# IDC_BNC_Adapter.net
KiCad netlist of a schematic drawn in Altium Designer
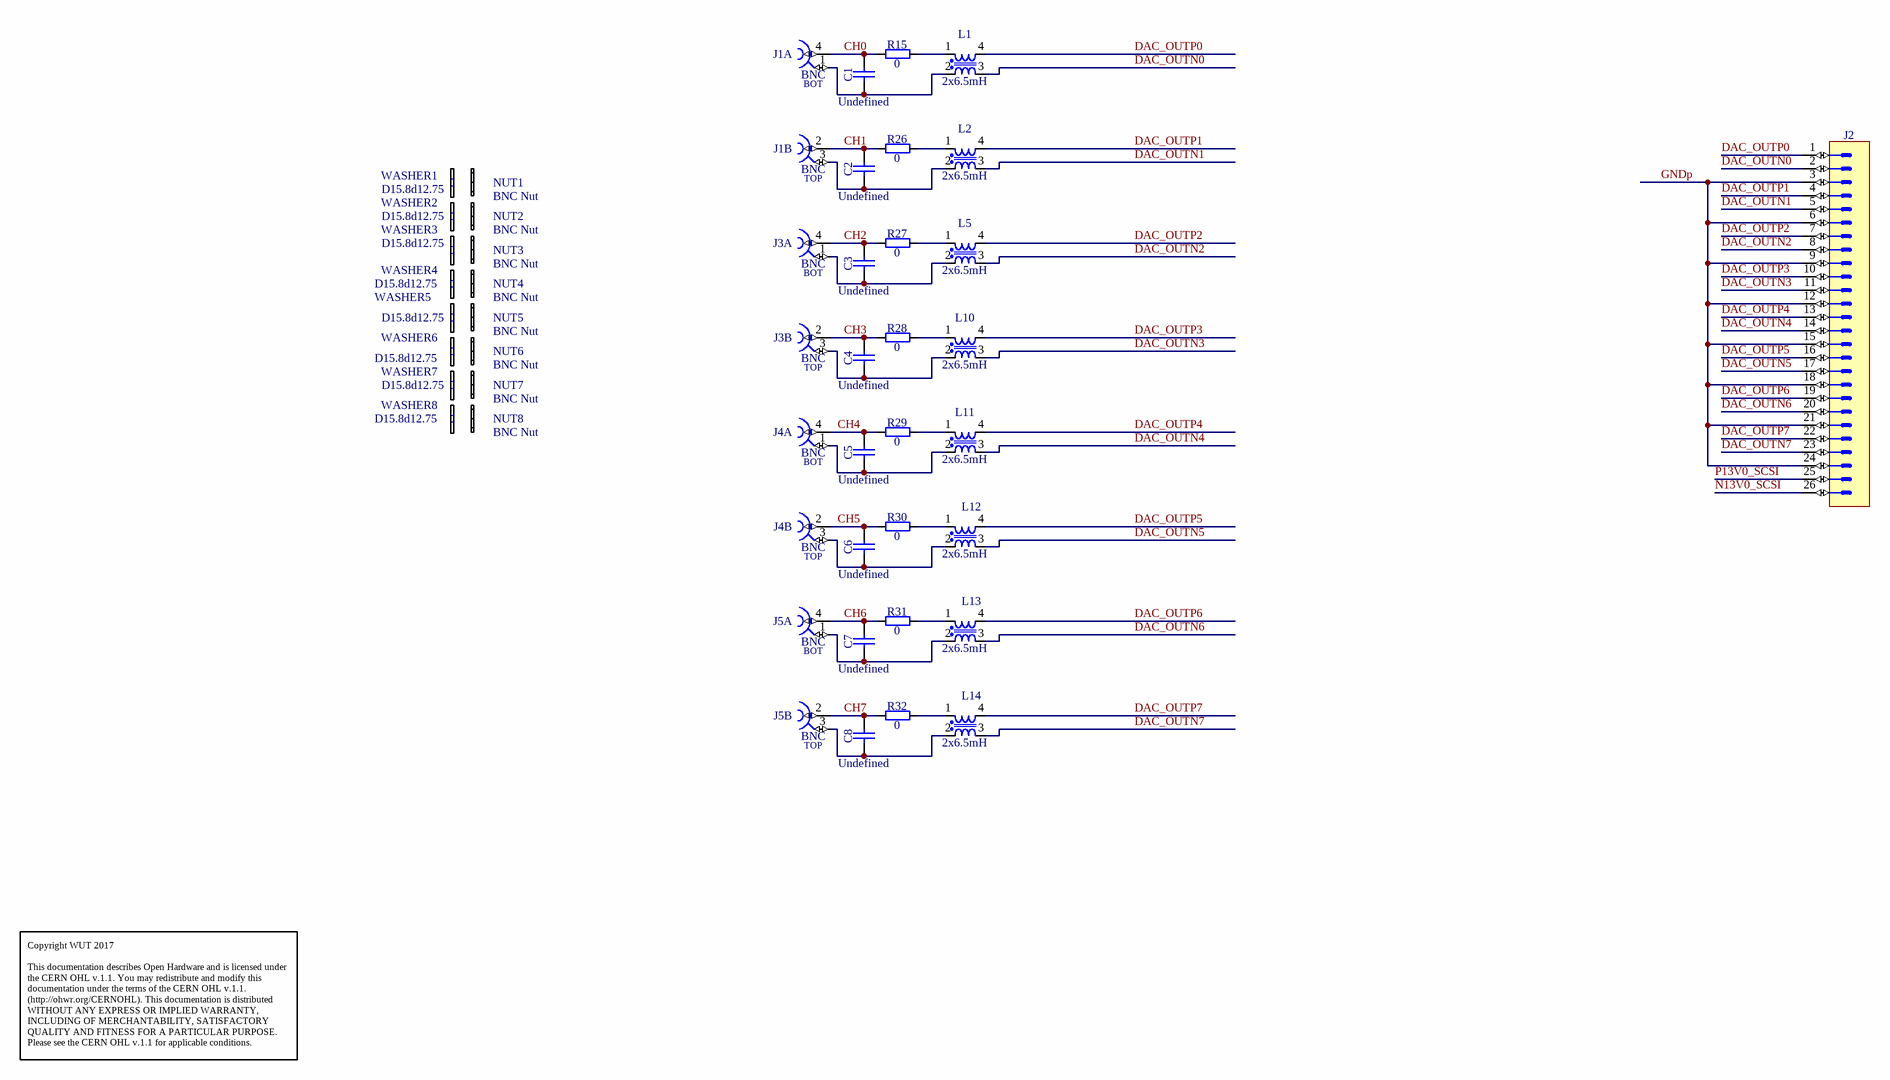
[diagram p0: IDC_BNC_Adapter.SchDoc]

(export (version "E")
  (design (tool "Eeschema 10.0.6"))
  (components
    (comp (ref "C1")
      (value "Undefined")
      (footprint "CAPC2012X135N")
      (description "Non-polarised capacitor")
      (fields (field (name "PART NUMBER") "CC0805_NO-VALUE") (field (name "AUTHOR") "CERN DEM JLC"))
      (libsource (lib "Capacitors") (part "Capacitor - non polarized"))
    )
    (comp (ref "C2")
      (value "Undefined")
      (footprint "CAPC2012X135N")
      (description "Non-polarised capacitor")
      (fields (field (name "PART NUMBER") "CC0805_NO-VALUE") (field (name "AUTHOR") "CERN DEM JLC"))
      (libsource (lib "Capacitors") (part "Capacitor - non polarized"))
    )
    (comp (ref "C3")
      (value "Undefined")
      (footprint "CAPC2012X135N")
      (description "Non-polarised capacitor")
      (fields (field (name "PART NUMBER") "CC0805_NO-VALUE") (field (name "AUTHOR") "CERN DEM JLC"))
      (libsource (lib "Capacitors") (part "Capacitor - non polarized"))
    )
    (comp (ref "C4")
      (value "Undefined")
      (footprint "CAPC2012X135N")
      (description "Non-polarised capacitor")
      (fields (field (name "PART NUMBER") "CC0805_NO-VALUE") (field (name "AUTHOR") "CERN DEM JLC"))
      (libsource (lib "Capacitors") (part "Capacitor - non polarized"))
    )
    (comp (ref "C5")
      (value "Undefined")
      (footprint "CAPC2012X135N")
      (description "Non-polarised capacitor")
      (fields (field (name "PART NUMBER") "CC0805_NO-VALUE") (field (name "AUTHOR") "CERN DEM JLC"))
      (libsource (lib "Capacitors") (part "Capacitor - non polarized"))
    )
    (comp (ref "C6")
      (value "Undefined")
      (footprint "CAPC2012X135N")
      (description "Non-polarised capacitor")
      (fields (field (name "PART NUMBER") "CC0805_NO-VALUE") (field (name "AUTHOR") "CERN DEM JLC"))
      (libsource (lib "Capacitors") (part "Capacitor - non polarized"))
    )
    (comp (ref "C7")
      (value "Undefined")
      (footprint "CAPC2012X135N")
      (description "Non-polarised capacitor")
      (fields (field (name "PART NUMBER") "CC0805_NO-VALUE") (field (name "AUTHOR") "CERN DEM JLC"))
      (libsource (lib "Capacitors") (part "Capacitor - non polarized"))
    )
    (comp (ref "C8")
      (value "Undefined")
      (footprint "CAPC2012X135N")
      (description "Non-polarised capacitor")
      (fields (field (name "PART NUMBER") "CC0805_NO-VALUE") (field (name "AUTHOR") "CERN DEM JLC"))
      (libsource (lib "Capacitors") (part "Capacitor - non polarized"))
    )
    (comp (ref "J1")
      (value "BNC")
      (footprint "RENHOTEC_RHT-610-0049")
      (description "Dual Right Angle 50 Ohm BNC Jack, White Valox Case")
      (fields
        (field (name "PART NUMBER") "RENHOTEC_RHT-610-0049")
        (field (name "MANUFACTURER") "RENHOTEC")
        (field (name "AUTHOR") "GK")
      )
      (libsource (lib "LIBRARY_SCH") (part "CON_BNC_DUAL"))
    )
    (comp (ref "J2")
      (value "Header 26")
      (footprint "3M_N2526-6003RB")
      (description "Connector 26 Male")
      (fields
        (field (name "PART NUMBER") "3M_N2526-6003RB")
        (field (name "MANUFACTURER") "3M")
        (field (name "AUTHOR") "CERN DEM JLC")
      )
      (libsource (lib "Connectors") (part "Connector 26 Male"))
    )
    (comp (ref "J3")
      (value "BNC")
      (footprint "RENHOTEC_RHT-610-0049")
      (description "Dual Right Angle 50 Ohm BNC Jack, White Valox Case")
      (fields
        (field (name "PART NUMBER") "RENHOTEC_RHT-610-0049")
        (field (name "MANUFACTURER") "RENHOTEC")
        (field (name "AUTHOR") "GK")
      )
      (libsource (lib "LIBRARY_SCH") (part "CON_BNC_DUAL"))
    )
    (comp (ref "J4")
      (value "BNC")
      (footprint "RENHOTEC_RHT-610-0049")
      (description "Dual Right Angle 50 Ohm BNC Jack, White Valox Case")
      (fields
        (field (name "PART NUMBER") "RENHOTEC_RHT-610-0049")
        (field (name "MANUFACTURER") "RENHOTEC")
        (field (name "AUTHOR") "GK")
      )
      (libsource (lib "LIBRARY_SCH") (part "CON_BNC_DUAL"))
    )
    (comp (ref "J5")
      (value "BNC")
      (footprint "RENHOTEC_RHT-610-0049")
      (description "Dual Right Angle 50 Ohm BNC Jack, White Valox Case")
      (fields
        (field (name "PART NUMBER") "RENHOTEC_RHT-610-0049")
        (field (name "MANUFACTURER") "RENHOTEC")
        (field (name "AUTHOR") "GK")
      )
      (libsource (lib "LIBRARY_SCH") (part "CON_BNC_DUAL"))
    )
    (comp (ref "L1")
      (value "2x6.5mH")
      (footprint "IND_WURTH_WE-SL2")
      (description "Inductor Common Mode")
      (fields
        (field (name "PART NUMBER") "IND_6.5MH_50%_WURTH_WE-SL2-744229")
        (field (name "POWER") "400mA")
        (field (name "AUTHOR") "CERN DEM JLC")
      )
      (libsource (lib "Inductors & Transformers") (part "Inductor Common Mode 1Dot-4 2Dot-3"))
    )
    (comp (ref "L2")
      (value "2x6.5mH")
      (footprint "IND_WURTH_WE-SL2")
      (description "Inductor Common Mode")
      (fields
        (field (name "PART NUMBER") "IND_6.5MH_50%_WURTH_WE-SL2-744229")
        (field (name "POWER") "400mA")
        (field (name "AUTHOR") "CERN DEM JLC")
      )
      (libsource (lib "Inductors & Transformers") (part "Inductor Common Mode 1Dot-4 2Dot-3"))
    )
    (comp (ref "L5")
      (value "2x6.5mH")
      (footprint "IND_WURTH_WE-SL2")
      (description "Inductor Common Mode")
      (fields
        (field (name "PART NUMBER") "IND_6.5MH_50%_WURTH_WE-SL2-744229")
        (field (name "POWER") "400mA")
        (field (name "AUTHOR") "CERN DEM JLC")
      )
      (libsource (lib "Inductors & Transformers") (part "Inductor Common Mode 1Dot-4 2Dot-3"))
    )
    (comp (ref "L10")
      (value "2x6.5mH")
      (footprint "IND_WURTH_WE-SL2")
      (description "Inductor Common Mode")
      (fields
        (field (name "PART NUMBER") "IND_6.5MH_50%_WURTH_WE-SL2-744229")
        (field (name "POWER") "400mA")
        (field (name "AUTHOR") "CERN DEM JLC")
      )
      (libsource (lib "Inductors & Transformers") (part "Inductor Common Mode 1Dot-4 2Dot-3"))
    )
    (comp (ref "L11")
      (value "2x6.5mH")
      (footprint "IND_WURTH_WE-SL2")
      (description "Inductor Common Mode")
      (fields
        (field (name "PART NUMBER") "IND_6.5MH_50%_WURTH_WE-SL2-744229")
        (field (name "POWER") "400mA")
        (field (name "AUTHOR") "CERN DEM JLC")
      )
      (libsource (lib "Inductors & Transformers") (part "Inductor Common Mode 1Dot-4 2Dot-3"))
    )
    (comp (ref "L12")
      (value "2x6.5mH")
      (footprint "IND_WURTH_WE-SL2")
      (description "Inductor Common Mode")
      (fields
        (field (name "PART NUMBER") "IND_6.5MH_50%_WURTH_WE-SL2-744229")
        (field (name "POWER") "400mA")
        (field (name "AUTHOR") "CERN DEM JLC")
      )
      (libsource (lib "Inductors & Transformers") (part "Inductor Common Mode 1Dot-4 2Dot-3"))
    )
    (comp (ref "L13")
      (value "2x6.5mH")
      (footprint "IND_WURTH_WE-SL2")
      (description "Inductor Common Mode")
      (fields
        (field (name "PART NUMBER") "IND_6.5MH_50%_WURTH_WE-SL2-744229")
        (field (name "POWER") "400mA")
        (field (name "AUTHOR") "CERN DEM JLC")
      )
      (libsource (lib "Inductors & Transformers") (part "Inductor Common Mode 1Dot-4 2Dot-3"))
    )
    (comp (ref "L14")
      (value "2x6.5mH")
      (footprint "IND_WURTH_WE-SL2")
      (description "Inductor Common Mode")
      (fields
        (field (name "PART NUMBER") "IND_6.5MH_50%_WURTH_WE-SL2-744229")
        (field (name "POWER") "400mA")
        (field (name "AUTHOR") "CERN DEM JLC")
      )
      (libsource (lib "Inductors & Transformers") (part "Inductor Common Mode 1Dot-4 2Dot-3"))
    )
    (comp (ref "NUT1")
      (value "BNC Nut")
      (footprint "TE_1-329631-2")
      (description "BNC nut")
      (fields
        (field (name "PART NUMBER") "TE_1-329631-2")
        (field (name "MANUFACTURER") "TE")
        (field (name "AUTHOR") "CERN DEM JLC")
      )
      (libsource (lib "LIBRARY_SCH") (part "MECH_BNC_NUT"))
    )
    (comp (ref "NUT2")
      (value "BNC Nut")
      (footprint "TE_1-329631-2")
      (description "BNC nut")
      (fields
        (field (name "PART NUMBER") "TE_1-329631-2")
        (field (name "MANUFACTURER") "TE")
        (field (name "AUTHOR") "CERN DEM JLC")
      )
      (libsource (lib "LIBRARY_SCH") (part "MECH_BNC_NUT"))
    )
    (comp (ref "NUT3")
      (value "BNC Nut")
      (footprint "TE_1-329631-2")
      (description "BNC nut")
      (fields
        (field (name "PART NUMBER") "TE_1-329631-2")
        (field (name "MANUFACTURER") "TE")
        (field (name "AUTHOR") "CERN DEM JLC")
      )
      (libsource (lib "LIBRARY_SCH") (part "MECH_BNC_NUT"))
    )
    (comp (ref "NUT4")
      (value "BNC Nut")
      (footprint "TE_1-329631-2")
      (description "BNC nut")
      (fields
        (field (name "PART NUMBER") "TE_1-329631-2")
        (field (name "MANUFACTURER") "TE")
        (field (name "AUTHOR") "CERN DEM JLC")
      )
      (libsource (lib "LIBRARY_SCH") (part "MECH_BNC_NUT"))
    )
    (comp (ref "NUT5")
      (value "BNC Nut")
      (footprint "TE_1-329631-2")
      (description "BNC nut")
      (fields
        (field (name "PART NUMBER") "TE_1-329631-2")
        (field (name "MANUFACTURER") "TE")
        (field (name "AUTHOR") "CERN DEM JLC")
      )
      (libsource (lib "LIBRARY_SCH") (part "MECH_BNC_NUT"))
    )
    (comp (ref "NUT6")
      (value "BNC Nut")
      (footprint "TE_1-329631-2")
      (description "BNC nut")
      (fields
        (field (name "PART NUMBER") "TE_1-329631-2")
        (field (name "MANUFACTURER") "TE")
        (field (name "AUTHOR") "CERN DEM JLC")
      )
      (libsource (lib "LIBRARY_SCH") (part "MECH_BNC_NUT"))
    )
    (comp (ref "NUT7")
      (value "BNC Nut")
      (footprint "TE_1-329631-2")
      (description "BNC nut")
      (fields
        (field (name "PART NUMBER") "TE_1-329631-2")
        (field (name "MANUFACTURER") "TE")
        (field (name "AUTHOR") "CERN DEM JLC")
      )
      (libsource (lib "LIBRARY_SCH") (part "MECH_BNC_NUT"))
    )
    (comp (ref "NUT8")
      (value "BNC Nut")
      (footprint "TE_1-329631-2")
      (description "BNC nut")
      (fields
        (field (name "PART NUMBER") "TE_1-329631-2")
        (field (name "MANUFACTURER") "TE")
        (field (name "AUTHOR") "CERN DEM JLC")
      )
      (libsource (lib "LIBRARY_SCH") (part "MECH_BNC_NUT"))
    )
    (comp (ref "R15")
      (value "0")
      (footprint "RESC1608X55N")
      (description "Resistor")
      (fields
        (field (name "PART NUMBER") "R0603_0R_JUMPER")
        (field (name "MANUFACTURER") "GENERIC")
        (field (name "AUTHOR") "CERN DEM JLC")
      )
      (libsource (lib "Resistors") (part "Resistor"))
    )
    (comp (ref "R26")
      (value "0")
      (footprint "RESC1608X55N")
      (description "Resistor")
      (fields
        (field (name "PART NUMBER") "R0603_0R_JUMPER")
        (field (name "MANUFACTURER") "GENERIC")
        (field (name "AUTHOR") "CERN DEM JLC")
      )
      (libsource (lib "Resistors") (part "Resistor"))
    )
    (comp (ref "R27")
      (value "0")
      (footprint "RESC1608X55N")
      (description "Resistor")
      (fields
        (field (name "PART NUMBER") "R0603_0R_JUMPER")
        (field (name "MANUFACTURER") "GENERIC")
        (field (name "AUTHOR") "CERN DEM JLC")
      )
      (libsource (lib "Resistors") (part "Resistor"))
    )
    (comp (ref "R28")
      (value "0")
      (footprint "RESC1608X55N")
      (description "Resistor")
      (fields
        (field (name "PART NUMBER") "R0603_0R_JUMPER")
        (field (name "MANUFACTURER") "GENERIC")
        (field (name "AUTHOR") "CERN DEM JLC")
      )
      (libsource (lib "Resistors") (part "Resistor"))
    )
    (comp (ref "R29")
      (value "0")
      (footprint "RESC1608X55N")
      (description "Resistor")
      (fields
        (field (name "PART NUMBER") "R0603_0R_JUMPER")
        (field (name "MANUFACTURER") "GENERIC")
        (field (name "AUTHOR") "CERN DEM JLC")
      )
      (libsource (lib "Resistors") (part "Resistor"))
    )
    (comp (ref "R30")
      (value "0")
      (footprint "RESC1608X55N")
      (description "Resistor")
      (fields
        (field (name "PART NUMBER") "R0603_0R_JUMPER")
        (field (name "MANUFACTURER") "GENERIC")
        (field (name "AUTHOR") "CERN DEM JLC")
      )
      (libsource (lib "Resistors") (part "Resistor"))
    )
    (comp (ref "R31")
      (value "0")
      (footprint "RESC1608X55N")
      (description "Resistor")
      (fields
        (field (name "PART NUMBER") "R0603_0R_JUMPER")
        (field (name "MANUFACTURER") "GENERIC")
        (field (name "AUTHOR") "CERN DEM JLC")
      )
      (libsource (lib "Resistors") (part "Resistor"))
    )
    (comp (ref "R32")
      (value "0")
      (footprint "RESC1608X55N")
      (description "Resistor")
      (fields
        (field (name "PART NUMBER") "R0603_0R_JUMPER")
        (field (name "MANUFACTURER") "GENERIC")
        (field (name "AUTHOR") "CERN DEM JLC")
      )
      (libsource (lib "Resistors") (part "Resistor"))
    )
    (comp (ref "WASHER1")
      (value "D15.8d12.75")
      (footprint "TE_1-1634817-0")
      (description "BNC Washer")
      (fields
        (field (name "PART NUMBER") "TE_1-1634817-0")
        (field (name "MANUFACTURER") "TE")
        (field (name "AUTHOR") "GK")
      )
      (libsource (lib "LIBRARY_SCH") (part "MECH_BNC_WASHER"))
    )
    (comp (ref "WASHER2")
      (value "D15.8d12.75")
      (footprint "TE_1-1634817-0")
      (description "BNC Washer")
      (fields
        (field (name "PART NUMBER") "TE_1-1634817-0")
        (field (name "MANUFACTURER") "TE")
        (field (name "AUTHOR") "GK")
      )
      (libsource (lib "LIBRARY_SCH") (part "MECH_BNC_WASHER"))
    )
    (comp (ref "WASHER3")
      (value "D15.8d12.75")
      (footprint "TE_1-1634817-0")
      (description "BNC Washer")
      (fields
        (field (name "PART NUMBER") "TE_1-1634817-0")
        (field (name "MANUFACTURER") "TE")
        (field (name "AUTHOR") "GK")
      )
      (libsource (lib "LIBRARY_SCH") (part "MECH_BNC_WASHER"))
    )
    (comp (ref "WASHER4")
      (value "D15.8d12.75")
      (footprint "TE_1-1634817-0")
      (description "BNC Washer")
      (fields
        (field (name "PART NUMBER") "TE_1-1634817-0")
        (field (name "MANUFACTURER") "TE")
        (field (name "AUTHOR") "GK")
      )
      (libsource (lib "LIBRARY_SCH") (part "MECH_BNC_WASHER"))
    )
    (comp (ref "WASHER5")
      (value "D15.8d12.75")
      (footprint "TE_1-1634817-0")
      (description "BNC Washer")
      (fields
        (field (name "PART NUMBER") "TE_1-1634817-0")
        (field (name "MANUFACTURER") "TE")
        (field (name "AUTHOR") "GK")
      )
      (libsource (lib "LIBRARY_SCH") (part "MECH_BNC_WASHER"))
    )
    (comp (ref "WASHER6")
      (value "D15.8d12.75")
      (footprint "TE_1-1634817-0")
      (description "BNC Washer")
      (fields
        (field (name "PART NUMBER") "TE_1-1634817-0")
        (field (name "MANUFACTURER") "TE")
        (field (name "AUTHOR") "GK")
      )
      (libsource (lib "LIBRARY_SCH") (part "MECH_BNC_WASHER"))
    )
    (comp (ref "WASHER7")
      (value "D15.8d12.75")
      (footprint "TE_1-1634817-0")
      (description "BNC Washer")
      (fields
        (field (name "PART NUMBER") "TE_1-1634817-0")
        (field (name "MANUFACTURER") "TE")
        (field (name "AUTHOR") "GK")
      )
      (libsource (lib "LIBRARY_SCH") (part "MECH_BNC_WASHER"))
    )
    (comp (ref "WASHER8")
      (value "D15.8d12.75")
      (footprint "TE_1-1634817-0")
      (description "BNC Washer")
      (fields
        (field (name "PART NUMBER") "TE_1-1634817-0")
        (field (name "MANUFACTURER") "TE")
        (field (name "AUTHOR") "GK")
      )
      (libsource (lib "LIBRARY_SCH") (part "MECH_BNC_WASHER"))
    )
  )
  (nets
    (net (code "1") (name "/CH0") (class "Default")
      (node (ref "C1") (pin "2") (pinfunction "2_2") (pintype "passive"))
      (node (ref "J1") (pin "4") (pinfunction "4_4") (pintype "bidirectional"))
      (node (ref "R15") (pin "1") (pinfunction "1_1") (pintype "passive"))
    )
    (net (code "2") (name "/CH1") (class "Default")
      (node (ref "C2") (pin "2") (pinfunction "2_2") (pintype "passive"))
      (node (ref "J1") (pin "2") (pinfunction "2_2") (pintype "bidirectional"))
      (node (ref "R26") (pin "1") (pinfunction "1_1") (pintype "passive"))
    )
    (net (code "3") (name "/CH2") (class "Default")
      (node (ref "C3") (pin "2") (pinfunction "2_2") (pintype "passive"))
      (node (ref "J3") (pin "4") (pinfunction "4_4") (pintype "bidirectional"))
      (node (ref "R27") (pin "1") (pinfunction "1_1") (pintype "passive"))
    )
    (net (code "4") (name "/CH3") (class "Default")
      (node (ref "C4") (pin "2") (pinfunction "2_2") (pintype "passive"))
      (node (ref "J3") (pin "2") (pinfunction "2_2") (pintype "bidirectional"))
      (node (ref "R28") (pin "1") (pinfunction "1_1") (pintype "passive"))
    )
    (net (code "5") (name "/CH4") (class "Default")
      (node (ref "C5") (pin "2") (pinfunction "2_2") (pintype "passive"))
      (node (ref "J4") (pin "4") (pinfunction "4_4") (pintype "bidirectional"))
      (node (ref "R29") (pin "1") (pinfunction "1_1") (pintype "passive"))
    )
    (net (code "6") (name "/CH5") (class "Default")
      (node (ref "C6") (pin "2") (pinfunction "2_2") (pintype "passive"))
      (node (ref "J4") (pin "2") (pinfunction "2_2") (pintype "bidirectional"))
      (node (ref "R30") (pin "1") (pinfunction "1_1") (pintype "passive"))
    )
    (net (code "7") (name "/CH6") (class "Default")
      (node (ref "C7") (pin "2") (pinfunction "2_2") (pintype "passive"))
      (node (ref "J5") (pin "4") (pinfunction "4_4") (pintype "bidirectional"))
      (node (ref "R31") (pin "1") (pinfunction "1_1") (pintype "passive"))
    )
    (net (code "8") (name "/CH7") (class "Default")
      (node (ref "C8") (pin "2") (pinfunction "2_2") (pintype "passive"))
      (node (ref "J5") (pin "2") (pinfunction "2_2") (pintype "bidirectional"))
      (node (ref "R32") (pin "1") (pinfunction "1_1") (pintype "passive"))
    )
    (net (code "9") (name "/DAC_OUTN0") (class "Default")
      (node (ref "J2") (pin "2") (pinfunction "2_2") (pintype "bidirectional"))
      (node (ref "L1") (pin "3") (pinfunction "3_3") (pintype "passive"))
    )
    (net (code "10") (name "/DAC_OUTN1") (class "Default")
      (node (ref "J2") (pin "5") (pinfunction "5_5") (pintype "bidirectional"))
      (node (ref "L2") (pin "3") (pinfunction "3_3") (pintype "passive"))
    )
    (net (code "11") (name "/DAC_OUTN2") (class "Default")
      (node (ref "J2") (pin "8") (pinfunction "8_8") (pintype "bidirectional"))
      (node (ref "L5") (pin "3") (pinfunction "3_3") (pintype "passive"))
    )
    (net (code "12") (name "/DAC_OUTN3") (class "Default")
      (node (ref "J2") (pin "11") (pinfunction "11_11") (pintype "bidirectional"))
      (node (ref "L10") (pin "3") (pinfunction "3_3") (pintype "passive"))
    )
    (net (code "13") (name "/DAC_OUTN4") (class "Default")
      (node (ref "J2") (pin "14") (pinfunction "14_14") (pintype "bidirectional"))
      (node (ref "L11") (pin "3") (pinfunction "3_3") (pintype "passive"))
    )
    (net (code "14") (name "/DAC_OUTN5") (class "Default")
      (node (ref "J2") (pin "17") (pinfunction "17_17") (pintype "bidirectional"))
      (node (ref "L12") (pin "3") (pinfunction "3_3") (pintype "passive"))
    )
    (net (code "15") (name "/DAC_OUTN6") (class "Default")
      (node (ref "J2") (pin "20") (pinfunction "20_20") (pintype "bidirectional"))
      (node (ref "L13") (pin "3") (pinfunction "3_3") (pintype "passive"))
    )
    (net (code "16") (name "/DAC_OUTN7") (class "Default")
      (node (ref "J2") (pin "23") (pinfunction "23_23") (pintype "bidirectional"))
      (node (ref "L14") (pin "3") (pinfunction "3_3") (pintype "passive"))
    )
    (net (code "17") (name "/DAC_OUTP0") (class "Default")
      (node (ref "J2") (pin "1") (pinfunction "1_1") (pintype "bidirectional"))
      (node (ref "L1") (pin "4") (pinfunction "4_4") (pintype "passive"))
    )
    (net (code "18") (name "/DAC_OUTP1") (class "Default")
      (node (ref "J2") (pin "4") (pinfunction "4_4") (pintype "bidirectional"))
      (node (ref "L2") (pin "4") (pinfunction "4_4") (pintype "passive"))
    )
    (net (code "19") (name "/DAC_OUTP2") (class "Default")
      (node (ref "J2") (pin "7") (pinfunction "7_7") (pintype "bidirectional"))
      (node (ref "L5") (pin "4") (pinfunction "4_4") (pintype "passive"))
    )
    (net (code "20") (name "/DAC_OUTP3") (class "Default")
      (node (ref "J2") (pin "10") (pinfunction "10_10") (pintype "bidirectional"))
      (node (ref "L10") (pin "4") (pinfunction "4_4") (pintype "passive"))
    )
    (net (code "21") (name "/DAC_OUTP4") (class "Default")
      (node (ref "J2") (pin "13") (pinfunction "13_13") (pintype "bidirectional"))
      (node (ref "L11") (pin "4") (pinfunction "4_4") (pintype "passive"))
    )
    (net (code "22") (name "/DAC_OUTP5") (class "Default")
      (node (ref "J2") (pin "16") (pinfunction "16_16") (pintype "bidirectional"))
      (node (ref "L12") (pin "4") (pinfunction "4_4") (pintype "passive"))
    )
    (net (code "23") (name "/DAC_OUTP6") (class "Default")
      (node (ref "J2") (pin "19") (pinfunction "19_19") (pintype "bidirectional"))
      (node (ref "L13") (pin "4") (pinfunction "4_4") (pintype "passive"))
    )
    (net (code "24") (name "/DAC_OUTP7") (class "Default")
      (node (ref "J2") (pin "22") (pinfunction "22_22") (pintype "bidirectional"))
      (node (ref "L14") (pin "4") (pinfunction "4_4") (pintype "passive"))
    )
    (net (code "25") (name "/GNDp") (class "Default")
      (node (ref "J2") (pin "12") (pinfunction "12_12") (pintype "bidirectional"))
      (node (ref "J2") (pin "15") (pinfunction "15_15") (pintype "bidirectional"))
      (node (ref "J2") (pin "18") (pinfunction "18_18") (pintype "bidirectional"))
      (node (ref "J2") (pin "21") (pinfunction "21_21") (pintype "bidirectional"))
      (node (ref "J2") (pin "24") (pinfunction "24_24") (pintype "bidirectional"))
      (node (ref "J2") (pin "3") (pinfunction "3_3") (pintype "bidirectional"))
      (node (ref "J2") (pin "6") (pinfunction "6_6") (pintype "bidirectional"))
      (node (ref "J2") (pin "9") (pinfunction "9_9") (pintype "bidirectional"))
    )
    (net (code "26") (name "/N13V0_SCSI") (class "Default")
      (node (ref "J2") (pin "26") (pinfunction "26_26") (pintype "bidirectional"))
    )
    (net (code "27") (name "/P13V0_SCSI") (class "Default")
      (node (ref "J2") (pin "25") (pinfunction "25_25") (pintype "bidirectional"))
    )
    (net (code "28") (name "Net-(C1-Pad1)") (class "Default")
      (node (ref "C1") (pin "1") (pinfunction "1_1") (pintype "passive"))
      (node (ref "J1") (pin "1") (pinfunction "1_1") (pintype "bidirectional"))
      (node (ref "L1") (pin "2") (pinfunction "2_2") (pintype "passive"))
    )
    (net (code "29") (name "Net-(C2-Pad1)") (class "Default")
      (node (ref "C2") (pin "1") (pinfunction "1_1") (pintype "passive"))
      (node (ref "J1") (pin "3") (pinfunction "3_3") (pintype "bidirectional"))
      (node (ref "L2") (pin "2") (pinfunction "2_2") (pintype "passive"))
    )
    (net (code "30") (name "Net-(C3-Pad1)") (class "Default")
      (node (ref "C3") (pin "1") (pinfunction "1_1") (pintype "passive"))
      (node (ref "J3") (pin "1") (pinfunction "1_1") (pintype "bidirectional"))
      (node (ref "L5") (pin "2") (pinfunction "2_2") (pintype "passive"))
    )
    (net (code "31") (name "Net-(C4-Pad1)") (class "Default")
      (node (ref "C4") (pin "1") (pinfunction "1_1") (pintype "passive"))
      (node (ref "J3") (pin "3") (pinfunction "3_3") (pintype "bidirectional"))
      (node (ref "L10") (pin "2") (pinfunction "2_2") (pintype "passive"))
    )
    (net (code "32") (name "Net-(C5-Pad1)") (class "Default")
      (node (ref "C5") (pin "1") (pinfunction "1_1") (pintype "passive"))
      (node (ref "J4") (pin "1") (pinfunction "1_1") (pintype "bidirectional"))
      (node (ref "L11") (pin "2") (pinfunction "2_2") (pintype "passive"))
    )
    (net (code "33") (name "Net-(C6-Pad1)") (class "Default")
      (node (ref "C6") (pin "1") (pinfunction "1_1") (pintype "passive"))
      (node (ref "J4") (pin "3") (pinfunction "3_3") (pintype "bidirectional"))
      (node (ref "L12") (pin "2") (pinfunction "2_2") (pintype "passive"))
    )
    (net (code "34") (name "Net-(C7-Pad1)") (class "Default")
      (node (ref "C7") (pin "1") (pinfunction "1_1") (pintype "passive"))
      (node (ref "J5") (pin "1") (pinfunction "1_1") (pintype "bidirectional"))
      (node (ref "L13") (pin "2") (pinfunction "2_2") (pintype "passive"))
    )
    (net (code "35") (name "Net-(C8-Pad1)") (class "Default")
      (node (ref "C8") (pin "1") (pinfunction "1_1") (pintype "passive"))
      (node (ref "J5") (pin "3") (pinfunction "3_3") (pintype "bidirectional"))
      (node (ref "L14") (pin "2") (pinfunction "2_2") (pintype "passive"))
    )
    (net (code "36") (name "Net-(L1-Pad1)") (class "Default")
      (node (ref "L1") (pin "1") (pinfunction "1_1") (pintype "passive"))
      (node (ref "R15") (pin "2") (pinfunction "2_2") (pintype "passive"))
    )
    (net (code "37") (name "Net-(L2-Pad1)") (class "Default")
      (node (ref "L2") (pin "1") (pinfunction "1_1") (pintype "passive"))
      (node (ref "R26") (pin "2") (pinfunction "2_2") (pintype "passive"))
    )
    (net (code "38") (name "Net-(L5-Pad1)") (class "Default")
      (node (ref "L5") (pin "1") (pinfunction "1_1") (pintype "passive"))
      (node (ref "R27") (pin "2") (pinfunction "2_2") (pintype "passive"))
    )
    (net (code "39") (name "Net-(L10-Pad1)") (class "Default")
      (node (ref "L10") (pin "1") (pinfunction "1_1") (pintype "passive"))
      (node (ref "R28") (pin "2") (pinfunction "2_2") (pintype "passive"))
    )
    (net (code "40") (name "Net-(L11-Pad1)") (class "Default")
      (node (ref "L11") (pin "1") (pinfunction "1_1") (pintype "passive"))
      (node (ref "R29") (pin "2") (pinfunction "2_2") (pintype "passive"))
    )
    (net (code "41") (name "Net-(L12-Pad1)") (class "Default")
      (node (ref "L12") (pin "1") (pinfunction "1_1") (pintype "passive"))
      (node (ref "R30") (pin "2") (pinfunction "2_2") (pintype "passive"))
    )
    (net (code "42") (name "Net-(L13-Pad1)") (class "Default")
      (node (ref "L13") (pin "1") (pinfunction "1_1") (pintype "passive"))
      (node (ref "R31") (pin "2") (pinfunction "2_2") (pintype "passive"))
    )
    (net (code "43") (name "Net-(L14-Pad1)") (class "Default")
      (node (ref "L14") (pin "1") (pinfunction "1_1") (pintype "passive"))
      (node (ref "R32") (pin "2") (pinfunction "2_2") (pintype "passive"))
    )
  )
)
